# pca64142.net
KiCad netlist of a schematic drawn in Altium Designer
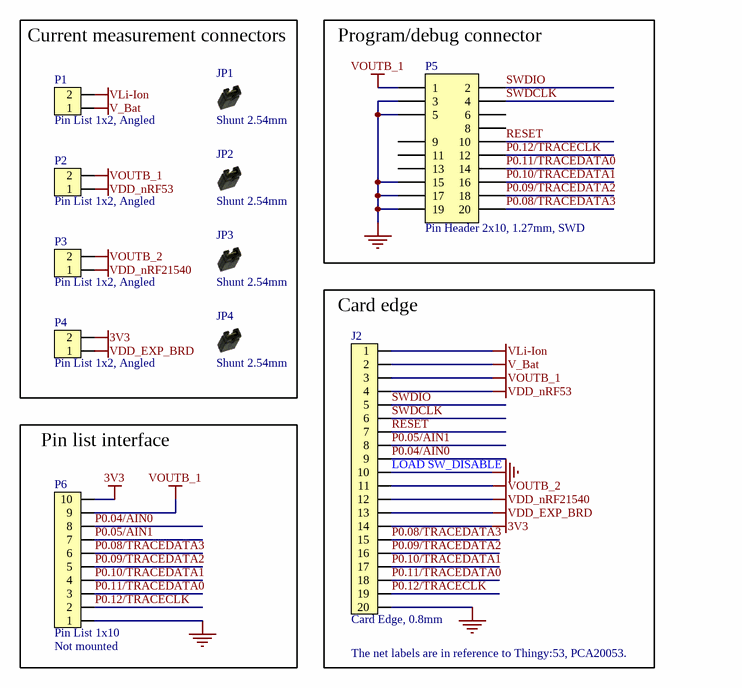
[diagram p0: pca64142.SchDoc]

(export (version "E")
  (design (tool "Eeschema 10.0.6"))
  (components
    (comp (ref "J2")
      (value "Card Edge, 0.8mm")
      (footprint "10056847-101LF Mating Board")
      (description "0.8mm pitch, dual edge, card edge connector")
      (fields (field (name "PART NUMBER") "10056847-101LF Mating Board") (field (name "MANUFACTURER") "N.A."))
      (libsource (lib "AltiumLib") (part "CONN-20"))
    )
    (comp (ref "JP1")
      (value "Shunt 2.54mm")
      (footprint "Shunt_2.54mm_Horizontal")
      (description "Shunt Jumper 2.54mm Black, open top")
      (fields
        (field (name "PART NUMBER") "SHUNT JUMPER 2.54mm Black Tin")
        (field (name "MANUFACTURER") "Samtec")
        (field (name "AUTHOR") "masi")
      )
      (libsource (lib "AltiumLib") (part "Shunt_Jumper_2.54"))
    )
    (comp (ref "JP2")
      (value "Shunt 2.54mm")
      (footprint "Shunt_2.54mm_Horizontal")
      (description "Shunt Jumper 2.54mm Black, open top")
      (fields
        (field (name "PART NUMBER") "SHUNT JUMPER 2.54mm Black Tin")
        (field (name "MANUFACTURER") "Samtec")
        (field (name "AUTHOR") "masi")
      )
      (libsource (lib "AltiumLib") (part "Shunt_Jumper_2.54"))
    )
    (comp (ref "JP3")
      (value "Shunt 2.54mm")
      (footprint "Shunt_2.54mm_Horizontal")
      (description "Shunt Jumper 2.54mm Black, open top")
      (fields
        (field (name "PART NUMBER") "SHUNT JUMPER 2.54mm Black Tin")
        (field (name "MANUFACTURER") "Samtec")
        (field (name "AUTHOR") "masi")
      )
      (libsource (lib "AltiumLib") (part "Shunt_Jumper_2.54"))
    )
    (comp (ref "JP4")
      (value "Shunt 2.54mm")
      (footprint "Shunt_2.54mm_Horizontal")
      (description "Shunt Jumper 2.54mm Black, open top")
      (fields
        (field (name "PART NUMBER") "SHUNT JUMPER 2.54mm Black Tin")
        (field (name "MANUFACTURER") "Samtec")
        (field (name "AUTHOR") "masi")
      )
      (libsource (lib "AltiumLib") (part "Shunt_Jumper_2.54"))
    )
    (comp (ref "P1")
      (value "Pin List 1x2, Angled")
      (footprint "LIST_ANG_1x2-SMD-2.54MM")
      (description "Pin List 1x2, 2.54mm (100mil), Right Angled, SMD")
      (fields
        (field (name "PART NUMBER") "Pin List Ang 1x2 SMD, 2.54mm")
        (field (name "MANUFACTURER") "W-CON")
      )
      (libsource (lib "AltiumLib") (part "CONN-2"))
    )
    (comp (ref "P2")
      (value "Pin List 1x2, Angled")
      (footprint "LIST_ANG_1x2-SMD-2.54MM")
      (description "Pin List 1x2, 2.54mm (100mil), Right Angled, SMD")
      (fields
        (field (name "PART NUMBER") "Pin List Ang 1x2 SMD, 2.54mm")
        (field (name "MANUFACTURER") "W-CON")
      )
      (libsource (lib "AltiumLib") (part "CONN-2"))
    )
    (comp (ref "P3")
      (value "Pin List 1x2, Angled")
      (footprint "LIST_ANG_1x2-SMD-2.54MM")
      (description "Pin List 1x2, 2.54mm (100mil), Right Angled, SMD")
      (fields
        (field (name "PART NUMBER") "Pin List Ang 1x2 SMD, 2.54mm")
        (field (name "MANUFACTURER") "W-CON")
      )
      (libsource (lib "AltiumLib") (part "CONN-2"))
    )
    (comp (ref "P4")
      (value "Pin List 1x2, Angled")
      (footprint "LIST_ANG_1x2-SMD-2.54MM")
      (description "Pin List 1x2, 2.54mm (100mil), Right Angled, SMD")
      (fields
        (field (name "PART NUMBER") "Pin List Ang 1x2 SMD, 2.54mm")
        (field (name "MANUFACTURER") "W-CON")
      )
      (libsource (lib "AltiumLib") (part "CONN-2"))
    )
    (comp (ref "P5")
      (value "Pin Header 2x10, 1.27mm, SWD")
      (footprint "HDR_2x10-SMD-1.27mm-K-SWD")
      (description "Pin Header 2x10, 1.27mm (50mil), SMD, Keying Shroud, Removed Pin 7")
      (fields
        (field (name "PART NUMBER") "Pin Header 2x10 SMD, 1.27mm, KS, SWD")
        (field (name "MANUFACTURER") "W-CON")
      )
      (libsource (lib "AltiumLib") (part "CONN-2x10-SWD"))
    )
    (comp (ref "P6")
      (value "Pin List 1x10")
      (footprint "LIST_1x10-NC")
      (description "Pin List 1x10, 2.54mm (100mil)")
      (fields
        (field (name "PART NUMBER") "Pin List 1x10, N.C.")
        (field (name "ASSEMBLY") "Not mounted")
        (field (name "MANUFACTURER") "N.A.")
      )
      (libsource (lib "AltiumLib") (part "CONN-10"))
    )
  )
  (nets
    (net (code "1") (name "/P0.04{slash}AIN0") (class "Default")
      (node (ref "J2") (pin "9") (pinfunction "9_9") (pintype "passive"))
      (node (ref "P6") (pin "8") (pinfunction "8_8") (pintype "passive"))
    )
    (net (code "2") (name "/P0.05{slash}AIN1") (class "Default")
      (node (ref "J2") (pin "8") (pinfunction "8_8") (pintype "passive"))
      (node (ref "P6") (pin "7") (pinfunction "7_7") (pintype "passive"))
    )
    (net (code "3") (name "/P0.08{slash}TRACEDATA3") (class "Default")
      (node (ref "J2") (pin "15") (pinfunction "15_15") (pintype "passive"))
      (node (ref "P5") (pin "20") (pinfunction "20_20") (pintype "passive"))
      (node (ref "P6") (pin "6") (pinfunction "6_6") (pintype "passive"))
    )
    (net (code "4") (name "/P0.09{slash}TRACEDATA2") (class "Default")
      (node (ref "J2") (pin "16") (pinfunction "16_16") (pintype "passive"))
      (node (ref "P5") (pin "18") (pinfunction "18_18") (pintype "passive"))
      (node (ref "P6") (pin "5") (pinfunction "5_5") (pintype "passive"))
    )
    (net (code "5") (name "/P0.10{slash}TRACEDATA1") (class "Default")
      (node (ref "J2") (pin "17") (pinfunction "17_17") (pintype "passive"))
      (node (ref "P5") (pin "16") (pinfunction "16_16") (pintype "passive"))
      (node (ref "P6") (pin "4") (pinfunction "4_4") (pintype "passive"))
    )
    (net (code "6") (name "/P0.11{slash}TRACEDATA0") (class "Default")
      (node (ref "J2") (pin "18") (pinfunction "18_18") (pintype "passive"))
      (node (ref "P5") (pin "14") (pinfunction "14_14") (pintype "passive"))
      (node (ref "P6") (pin "3") (pinfunction "3_3") (pintype "passive"))
    )
    (net (code "7") (name "/P0.12{slash}TRACECLK") (class "Default")
      (node (ref "J2") (pin "19") (pinfunction "19_19") (pintype "passive"))
      (node (ref "P5") (pin "12") (pinfunction "12_12") (pintype "passive"))
      (node (ref "P6") (pin "2") (pinfunction "2_2") (pintype "passive"))
    )
    (net (code "8") (name "/RESET") (class "Default")
      (node (ref "J2") (pin "7") (pinfunction "7_7") (pintype "passive"))
      (node (ref "P5") (pin "10") (pinfunction "10_10") (pintype "passive"))
    )
    (net (code "9") (name "/SWDCLK") (class "Default")
      (node (ref "J2") (pin "6") (pinfunction "6_6") (pintype "passive"))
      (node (ref "P5") (pin "4") (pinfunction "4_4") (pintype "passive"))
    )
    (net (code "10") (name "/SWDIO") (class "Default")
      (node (ref "J2") (pin "5") (pinfunction "5_5") (pintype "passive"))
      (node (ref "P5") (pin "2") (pinfunction "2_2") (pintype "passive"))
    )
    (net (code "11") (name "3V3") (class "Default")
      (node (ref "J2") (pin "14") (pinfunction "14_14") (pintype "passive"))
      (node (ref "P4") (pin "2") (pinfunction "2_2") (pintype "passive"))
      (node (ref "P6") (pin "10") (pinfunction "10_10") (pintype "passive"))
    )
    (net (code "12") (name "GND") (class "Default")
      (node (ref "J2") (pin "10") (pinfunction "10_10") (pintype "passive"))
      (node (ref "J2") (pin "20") (pinfunction "20_20") (pintype "passive"))
      (node (ref "P5") (pin "15") (pinfunction "15_15") (pintype "passive"))
      (node (ref "P5") (pin "17") (pinfunction "17_17") (pintype "passive"))
      (node (ref "P5") (pin "19") (pinfunction "19_19") (pintype "passive"))
      (node (ref "P5") (pin "3") (pinfunction "3_3") (pintype "passive"))
      (node (ref "P5") (pin "5") (pinfunction "5_5") (pintype "passive"))
      (node (ref "P6") (pin "1") (pinfunction "1_1") (pintype "passive"))
    )
    (net (code "13") (name "VDD_EXP_BRD") (class "Default")
      (node (ref "J2") (pin "13") (pinfunction "13_13") (pintype "passive"))
      (node (ref "P4") (pin "1") (pinfunction "1_1") (pintype "passive"))
    )
    (net (code "14") (name "VDD_nRF53") (class "Default")
      (node (ref "J2") (pin "4") (pinfunction "4_4") (pintype "passive"))
      (node (ref "P2") (pin "1") (pinfunction "1_1") (pintype "passive"))
    )
    (net (code "15") (name "VDD_nRF21540") (class "Default")
      (node (ref "J2") (pin "12") (pinfunction "12_12") (pintype "passive"))
      (node (ref "P3") (pin "1") (pinfunction "1_1") (pintype "passive"))
    )
    (net (code "16") (name "VLi-Ion") (class "Default")
      (node (ref "J2") (pin "1") (pinfunction "1_1") (pintype "passive"))
      (node (ref "P1") (pin "2") (pinfunction "2_2") (pintype "passive"))
    )
    (net (code "17") (name "VOUTB_1") (class "Default")
      (node (ref "J2") (pin "3") (pinfunction "3_3") (pintype "passive"))
      (node (ref "P2") (pin "2") (pinfunction "2_2") (pintype "passive"))
      (node (ref "P5") (pin "1") (pinfunction "1_1") (pintype "passive"))
      (node (ref "P6") (pin "9") (pinfunction "9_9") (pintype "passive"))
    )
    (net (code "18") (name "VOUTB_2") (class "Default")
      (node (ref "J2") (pin "11") (pinfunction "11_11") (pintype "passive"))
      (node (ref "P3") (pin "2") (pinfunction "2_2") (pintype "passive"))
    )
    (net (code "19") (name "V_Bat") (class "Default")
      (node (ref "J2") (pin "2") (pinfunction "2_2") (pintype "passive"))
      (node (ref "P1") (pin "1") (pinfunction "1_1") (pintype "passive"))
    )
    (net (code "20") (name "unconnected-(P5-Pad6)") (class "Default")
      (node (ref "P5") (pin "6") (pinfunction "6_6") (pintype "passive"))
    )
    (net (code "21") (name "unconnected-(P5-Pad8)") (class "Default")
      (node (ref "P5") (pin "8") (pinfunction "8_8") (pintype "passive"))
    )
    (net (code "22") (name "unconnected-(P5-Pad9)") (class "Default")
      (node (ref "P5") (pin "9") (pinfunction "9_9") (pintype "passive"))
    )
    (net (code "23") (name "unconnected-(P5-Pad11)") (class "Default")
      (node (ref "P5") (pin "11") (pinfunction "11_11") (pintype "passive"))
    )
    (net (code "24") (name "unconnected-(P5-Pad13)") (class "Default")
      (node (ref "P5") (pin "13") (pinfunction "13_13") (pintype "passive"))
    )
  )
)
